# motherboard.net
KiCad netlist of a schematic drawn in EAGLE
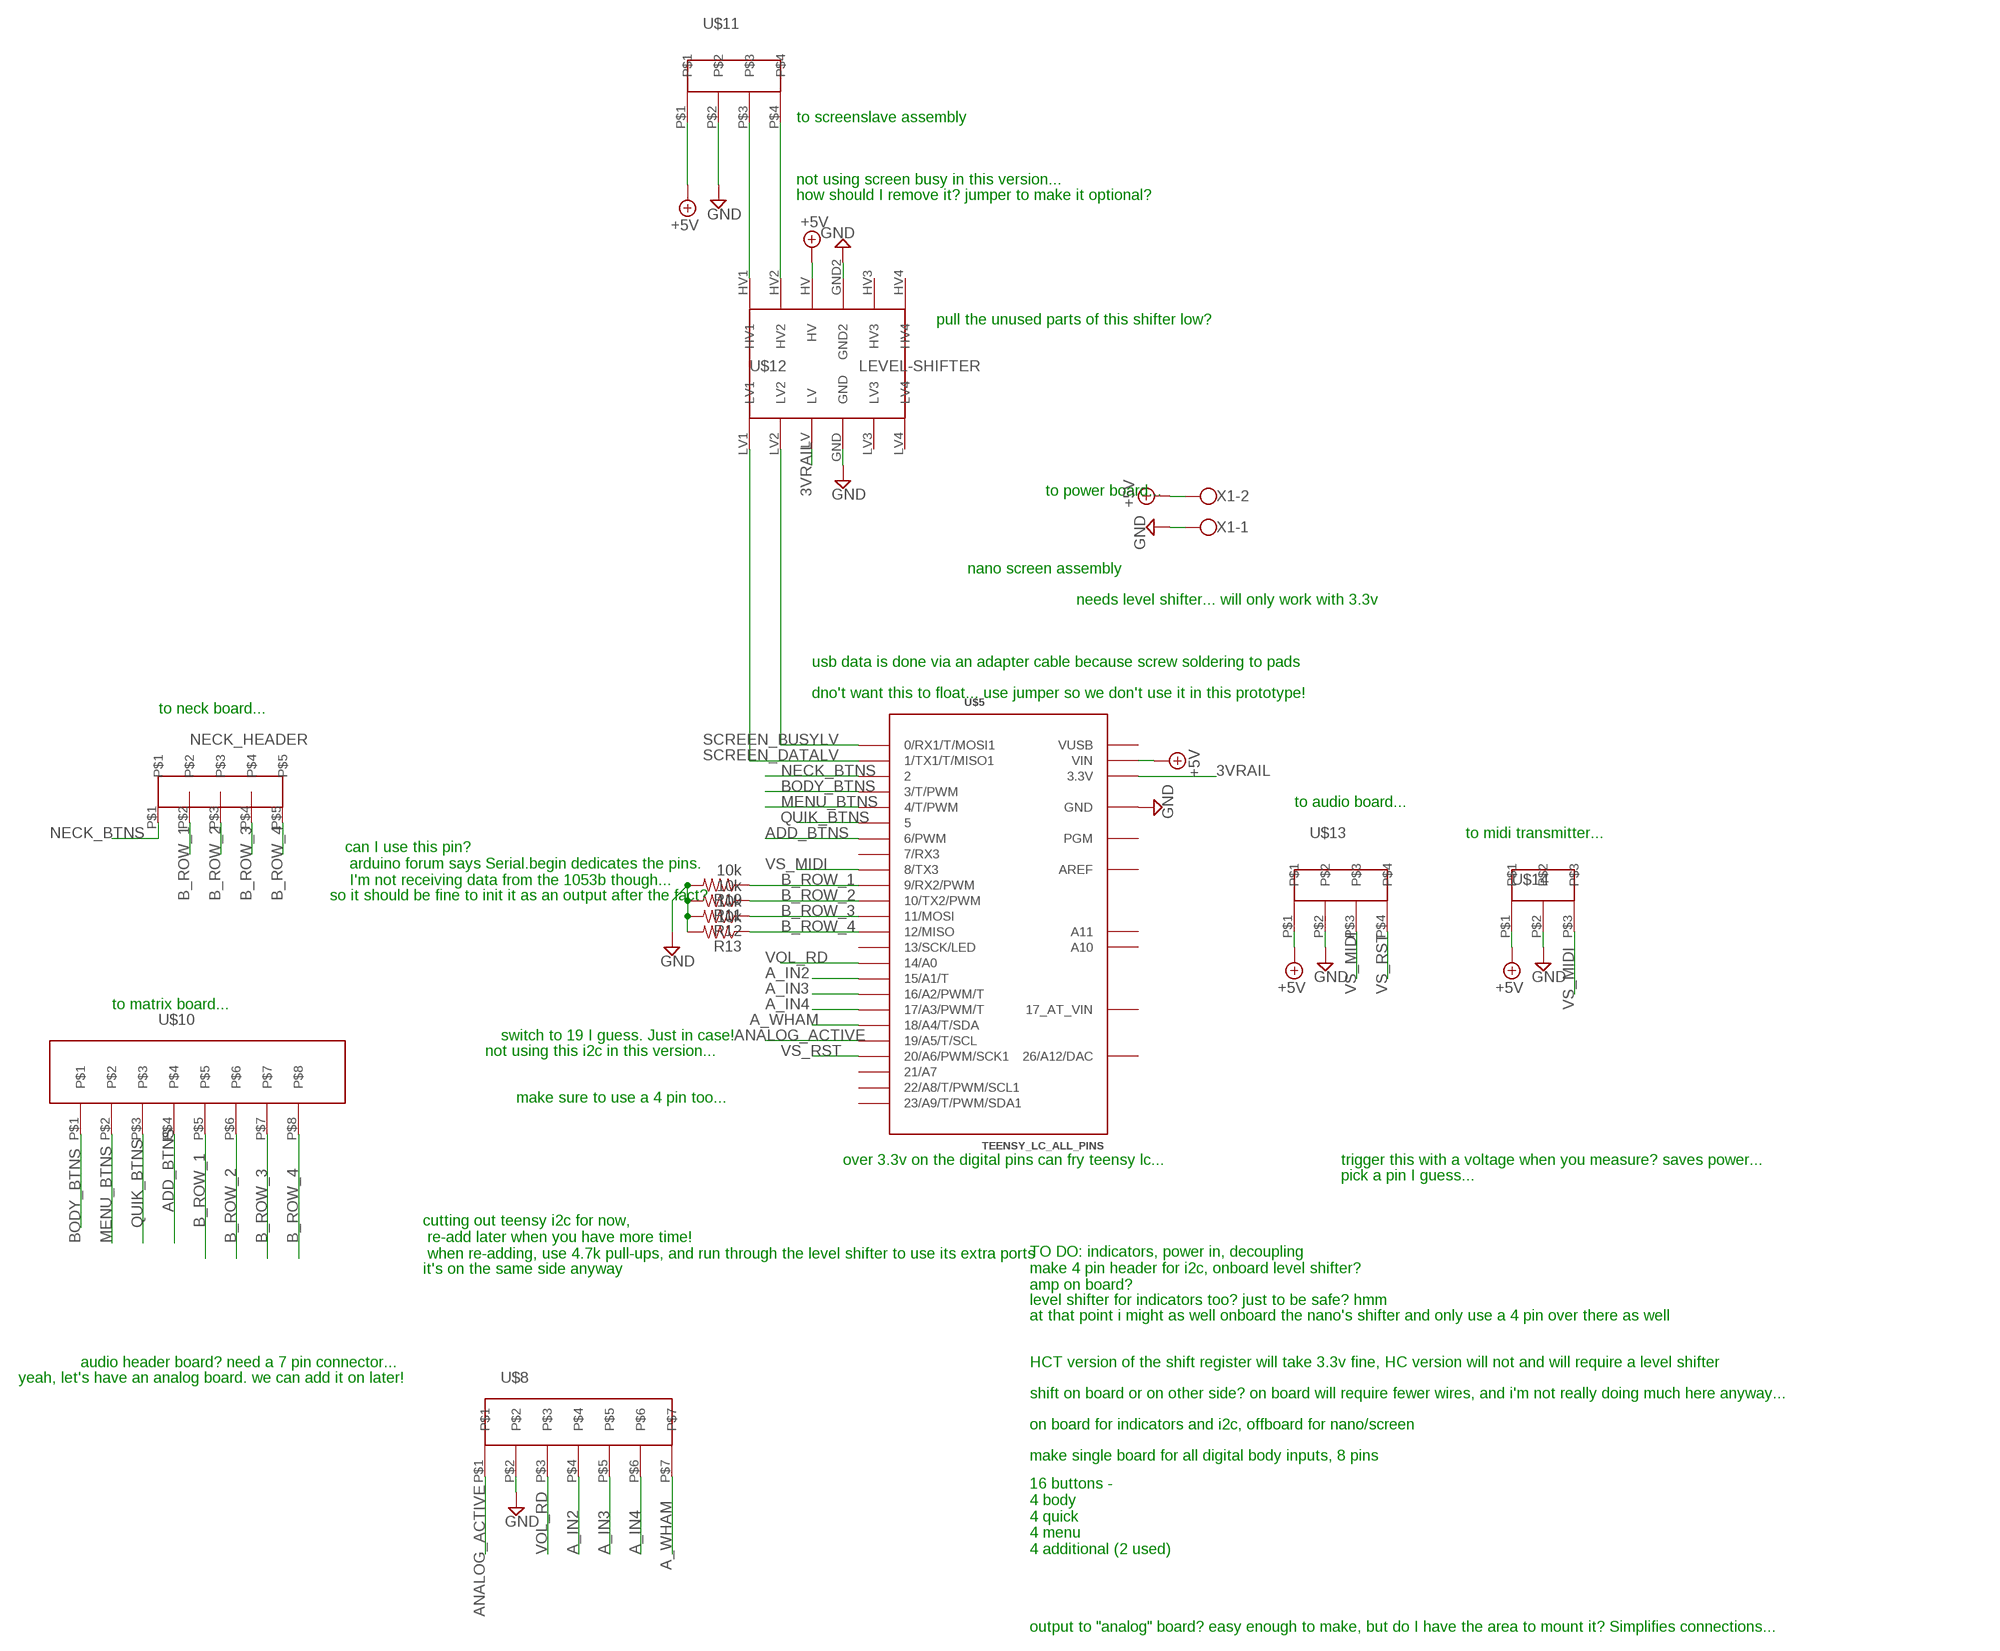
[diagram p0: schematic, sheet 1]

(export (version "E")
  (design (tool "Eeschema 10.0.6"))
  (components
    (comp (ref "NECK_HEADER")
      (value "5-PIN-HEADER")
      (footprint "eagle-import:5-PIN-HEADER")
      (libsource (lib "eagle-import") (part "5-PIN-HEADER"))
    )
    (comp (ref "R10")
      (value "10k")
      (footprint "eagle-import:0204_7")
      (libsource (lib "eagle-import") (part "R-US_0204/7"))
    )
    (comp (ref "R11")
      (value "10k")
      (footprint "eagle-import:0204_7")
      (libsource (lib "eagle-import") (part "R-US_0204/7"))
    )
    (comp (ref "R12")
      (value "10k")
      (footprint "eagle-import:0204_7")
      (libsource (lib "eagle-import") (part "R-US_0204/7"))
    )
    (comp (ref "R13")
      (value "10k")
      (footprint "eagle-import:0204_7")
      (libsource (lib "eagle-import") (part "R-US_0204/7"))
    )
    (comp (ref "U$5")
      (value "TEENSY_LC_ALL_PINS")
      (footprint "eagle-import:TEENSY_3.0-3.2&LC_ALL_PINS")
      (libsource (lib "eagle-import") (part "TEENSY_LC_ALL_PINS"))
    )
    (comp (ref "U$8")
      (value "7-PIN-HEADER")
      (footprint "eagle-import:7-PIN-HEADER")
      (libsource (lib "eagle-import") (part "7-PIN-HEADER"))
    )
    (comp (ref "U$10")
      (value "8-PIN-HEADER")
      (footprint "eagle-import:8-PIN-HEADER")
      (libsource (lib "eagle-import") (part "8-PIN-HEADER"))
    )
    (comp (ref "U$11")
      (value "4-PIN-HEADER")
      (footprint "eagle-import:4-PIN-HEADER")
      (libsource (lib "eagle-import") (part "4-PIN-HEADER"))
    )
    (comp (ref "U$12")
      (value "LEVEL-SHIFTER")
      (footprint "eagle-import:LEVEL-SHIFTER")
      (libsource (lib "eagle-import") (part "LEVEL-SHIFTER"))
    )
    (comp (ref "U$13")
      (value "4-PIN-HEADER")
      (footprint "eagle-import:4-PIN-HEADER")
      (libsource (lib "eagle-import") (part "4-PIN-HEADER"))
    )
    (comp (ref "U$14")
      (value "3-PIN-HEADER")
      (footprint "eagle-import:3-PIN-HEADER")
      (libsource (lib "eagle-import") (part "3-PIN-HEADER"))
    )
    (comp (ref "X1")
      (value "W237-102")
      (footprint "eagle-import:W237-102")
      (fields (field (name "MPN") "237-102"))
      (libsource (lib "eagle-import") (part "W237-102"))
    )
  )
  (nets
    (net (code "1") (name "+5V") (class "Default")
      (node (ref "U$11") (pin "P$1") (pinfunction "P$1_P$1") (pintype "bidirectional"))
      (node (ref "U$12") (pin "HV") (pinfunction "HV_HV") (pintype "bidirectional"))
      (node (ref "U$13") (pin "P$1") (pinfunction "P$1_P$1") (pintype "bidirectional"))
      (node (ref "U$14") (pin "P$1") (pinfunction "P$1_P$1") (pintype "bidirectional"))
      (node (ref "U$5") (pin "VIN") (pinfunction "VIN_VIN") (pintype "power_in"))
      (node (ref "X1") (pin "2") (pinfunction "KL_2") (pintype "passive"))
    )
    (net (code "2") (name "/3VRAIL") (class "Default")
      (node (ref "U$12") (pin "LV") (pinfunction "LV_LV") (pintype "bidirectional"))
      (node (ref "U$5") (pin "3.3V") (pinfunction "3.3V_3.3V") (pintype "power_in"))
      (node (ref "U$5") (pin "3.3V1") (pinfunction "3.3V_3.3V1") (pintype "power_in"))
    )
    (net (code "3") (name "/26{slash}A12{slash}DAC") (class "Default")
      (node (ref "U$5") (pin "RESET/DAC") (pinfunction "26/A12/DAC_RESET/DAC") (pintype "power_in"))
    )
    (net (code "4") (name "/ADD_BTNS") (class "Default")
      (node (ref "U$10") (pin "P$4") (pinfunction "P$4_P$4") (pintype "bidirectional"))
      (node (ref "U$5") (pin "6") (pinfunction "6/PWM_6") (pintype "bidirectional"))
    )
    (net (code "5") (name "/ANALOG_ACTIVE") (class "Default")
      (node (ref "U$5") (pin "19/A5") (pinfunction "19/A5/T/SCL_19/A5") (pintype "bidirectional"))
      (node (ref "U$8") (pin "P$1") (pinfunction "P$1_P$1") (pintype "bidirectional"))
    )
    (net (code "6") (name "/AREF") (class "Default")
      (node (ref "U$5") (pin "AREF") (pinfunction "AREF_AREF") (pintype "power_in"))
    )
    (net (code "7") (name "/A_IN2") (class "Default")
      (node (ref "U$5") (pin "15/A1") (pinfunction "15/A1/T_15/A1") (pintype "bidirectional"))
      (node (ref "U$8") (pin "P$4") (pinfunction "P$4_P$4") (pintype "bidirectional"))
    )
    (net (code "8") (name "/A_IN3") (class "Default")
      (node (ref "U$5") (pin "16/A2") (pinfunction "16/A2/PWM/T_16/A2") (pintype "bidirectional"))
      (node (ref "U$8") (pin "P$5") (pinfunction "P$5_P$5") (pintype "bidirectional"))
    )
    (net (code "9") (name "/A_IN4") (class "Default")
      (node (ref "U$5") (pin "17/A3") (pinfunction "17/A3/PWM/T_17/A3") (pintype "bidirectional"))
      (node (ref "U$8") (pin "P$6") (pinfunction "P$6_P$6") (pintype "bidirectional"))
    )
    (net (code "10") (name "/A_WHAM") (class "Default")
      (node (ref "U$5") (pin "18/A4") (pinfunction "18/A4/T/SDA_18/A4") (pintype "bidirectional"))
      (node (ref "U$8") (pin "P$7") (pinfunction "P$7_P$7") (pintype "bidirectional"))
    )
    (net (code "11") (name "/BODY_BTNS") (class "Default")
      (node (ref "U$10") (pin "P$1") (pinfunction "P$1_P$1") (pintype "bidirectional"))
      (node (ref "U$5") (pin "3") (pinfunction "3/T/PWM_3") (pintype "bidirectional"))
    )
    (net (code "12") (name "/B_ROW_1") (class "Default")
      (node (ref "NECK_HEADER") (pin "P$2") (pinfunction "P$2_P$2") (pintype "bidirectional"))
      (node (ref "R10") (pin "1") (pinfunction "1_1") (pintype "passive"))
      (node (ref "U$10") (pin "P$5") (pinfunction "P$5_P$5") (pintype "bidirectional"))
      (node (ref "U$5") (pin "9") (pinfunction "9/RX2/PWM_9") (pintype "bidirectional"))
    )
    (net (code "13") (name "/B_ROW_2") (class "Default")
      (node (ref "NECK_HEADER") (pin "P$3") (pinfunction "P$3_P$3") (pintype "bidirectional"))
      (node (ref "R11") (pin "1") (pinfunction "1_1") (pintype "passive"))
      (node (ref "U$10") (pin "P$6") (pinfunction "P$6_P$6") (pintype "bidirectional"))
      (node (ref "U$5") (pin "10") (pinfunction "10/TX2/PWM_10") (pintype "bidirectional"))
    )
    (net (code "14") (name "/B_ROW_3") (class "Default")
      (node (ref "NECK_HEADER") (pin "P$4") (pinfunction "P$4_P$4") (pintype "bidirectional"))
      (node (ref "R12") (pin "1") (pinfunction "1_1") (pintype "passive"))
      (node (ref "U$10") (pin "P$7") (pinfunction "P$7_P$7") (pintype "bidirectional"))
      (node (ref "U$5") (pin "11") (pinfunction "11/MOSI_11") (pintype "bidirectional"))
    )
    (net (code "15") (name "/B_ROW_4") (class "Default")
      (node (ref "NECK_HEADER") (pin "P$5") (pinfunction "P$5_P$5") (pintype "bidirectional"))
      (node (ref "R13") (pin "1") (pinfunction "1_1") (pintype "passive"))
      (node (ref "U$10") (pin "P$8") (pinfunction "P$8_P$8") (pintype "bidirectional"))
      (node (ref "U$5") (pin "12") (pinfunction "12/MISO_12") (pintype "bidirectional"))
    )
    (net (code "16") (name "/MENU_BTNS") (class "Default")
      (node (ref "U$10") (pin "P$2") (pinfunction "P$2_P$2") (pintype "bidirectional"))
      (node (ref "U$5") (pin "4") (pinfunction "4/T/PWM_4") (pintype "bidirectional"))
    )
    (net (code "17") (name "/NECK_BTNS") (class "Default")
      (node (ref "NECK_HEADER") (pin "P$1") (pinfunction "P$1_P$1") (pintype "bidirectional"))
      (node (ref "U$5") (pin "2") (pinfunction "2_2") (pintype "bidirectional"))
    )
    (net (code "18") (name "/QUIK_BTNS") (class "Default")
      (node (ref "U$10") (pin "P$3") (pinfunction "P$3_P$3") (pintype "bidirectional"))
      (node (ref "U$5") (pin "5") (pinfunction "5_5") (pintype "bidirectional"))
    )
    (net (code "19") (name "/SCREEN_BUSYLV") (class "Default")
      (node (ref "U$12") (pin "LV2") (pinfunction "LV2_LV2") (pintype "bidirectional"))
      (node (ref "U$5") (pin "0") (pinfunction "0/RX1/T/MOSI1_0") (pintype "bidirectional"))
    )
    (net (code "20") (name "/SCREEN_DATALV") (class "Default")
      (node (ref "U$12") (pin "LV1") (pinfunction "LV1_LV1") (pintype "bidirectional"))
      (node (ref "U$5") (pin "1") (pinfunction "1/TX1/T/MISO1_1") (pintype "bidirectional"))
    )
    (net (code "21") (name "/VOL_RD") (class "Default")
      (node (ref "U$5") (pin "14/A0") (pinfunction "14/A0_14/A0") (pintype "bidirectional"))
      (node (ref "U$8") (pin "P$3") (pinfunction "P$3_P$3") (pintype "bidirectional"))
    )
    (net (code "22") (name "/VS_MIDI") (class "Default")
      (node (ref "U$13") (pin "P$3") (pinfunction "P$3_P$3") (pintype "bidirectional"))
      (node (ref "U$14") (pin "P$3") (pinfunction "P$3_P$3") (pintype "bidirectional"))
      (node (ref "U$5") (pin "8") (pinfunction "8/TX3_8") (pintype "bidirectional"))
    )
    (net (code "23") (name "/VS_RST") (class "Default")
      (node (ref "U$13") (pin "P$4") (pinfunction "P$4_P$4") (pintype "bidirectional"))
      (node (ref "U$5") (pin "20/A6") (pinfunction "20/A6/PWM/SCK1_20/A6") (pintype "bidirectional"))
    )
    (net (code "24") (name "/VUSB") (class "Default")
      (node (ref "U$5") (pin "VUSB") (pinfunction "VUSB_VUSB") (pintype "power_in"))
    )
    (net (code "25") (name "GND") (class "Default")
      (node (ref "R10") (pin "2") (pinfunction "2_2") (pintype "passive"))
      (node (ref "R11") (pin "2") (pinfunction "2_2") (pintype "passive"))
      (node (ref "R12") (pin "2") (pinfunction "2_2") (pintype "passive"))
      (node (ref "R13") (pin "2") (pinfunction "2_2") (pintype "passive"))
      (node (ref "U$11") (pin "P$2") (pinfunction "P$2_P$2") (pintype "bidirectional"))
      (node (ref "U$12") (pin "GND") (pinfunction "GND_GND") (pintype "bidirectional"))
      (node (ref "U$12") (pin "GND2") (pinfunction "GND2_GND2") (pintype "bidirectional"))
      (node (ref "U$13") (pin "P$2") (pinfunction "P$2_P$2") (pintype "bidirectional"))
      (node (ref "U$14") (pin "P$2") (pinfunction "P$2_P$2") (pintype "bidirectional"))
      (node (ref "U$5") (pin "AGND") (pinfunction "GND_AGND") (pintype "power_in"))
      (node (ref "U$5") (pin "GND") (pinfunction "GND_GND") (pintype "power_in"))
      (node (ref "U$5") (pin "GND1") (pinfunction "GND_GND1") (pintype "power_in"))
      (node (ref "U$8") (pin "P$2") (pinfunction "P$2_P$2") (pintype "bidirectional"))
      (node (ref "X1") (pin "1") (pinfunction "KL_1") (pintype "passive"))
    )
    (net (code "26") (name "Net-(U$11-PadP$3)") (class "Default")
      (node (ref "U$11") (pin "P$3") (pinfunction "P$3_P$3") (pintype "bidirectional"))
      (node (ref "U$12") (pin "HV1") (pinfunction "HV1_HV1") (pintype "bidirectional"))
    )
    (net (code "27") (name "Net-(U$11-PadP$4)") (class "Default")
      (node (ref "U$11") (pin "P$4") (pinfunction "P$4_P$4") (pintype "bidirectional"))
      (node (ref "U$12") (pin "HV2") (pinfunction "HV2_HV2") (pintype "bidirectional"))
    )
    (net (code "28") (name "unconnected-(U$5-7{slash}RX3-Pad7)") (class "Default")
      (node (ref "U$5") (pin "7") (pinfunction "7/RX3_7") (pintype "bidirectional"))
    )
    (net (code "29") (name "unconnected-(U$5-13{slash}SCK{slash}LED-Pad13)") (class "Default")
      (node (ref "U$5") (pin "13") (pinfunction "13/SCK/LED_13") (pintype "bidirectional"))
    )
    (net (code "30") (name "unconnected-(U$5-17_AT_VIN-PadVBAT)") (class "Default")
      (node (ref "U$5") (pin "VBAT") (pinfunction "17_AT_VIN_VBAT") (pintype "bidirectional"))
    )
    (net (code "31") (name "unconnected-(U$5-22{slash}A8{slash}T{slash}PWM{slash}SCL1-Pad22{slash}A8)") (class "Default")
      (node (ref "U$5") (pin "22/A8") (pinfunction "22/A8/T/PWM/SCL1_22/A8") (pintype "bidirectional"))
    )
    (net (code "32") (name "unconnected-(U$5-23{slash}A9{slash}T{slash}PWM{slash}SDA1-Pad23{slash}A9)") (class "Default")
      (node (ref "U$5") (pin "23/A9") (pinfunction "23/A9/T/PWM/SDA1_23/A9") (pintype "bidirectional"))
    )
    (net (code "33") (name "unconnected-(U$5-Pad21{slash}A7)") (class "Default")
      (node (ref "U$5") (pin "21/A7") (pinfunction "21/A7_21/A7") (pintype "bidirectional"))
    )
    (net (code "34") (name "unconnected-(U$5-PadA10)") (class "Default")
      (node (ref "U$5") (pin "A10") (pinfunction "A10_A10") (pintype "bidirectional"))
    )
    (net (code "35") (name "unconnected-(U$5-PadA11)") (class "Default")
      (node (ref "U$5") (pin "A11") (pinfunction "A11_A11") (pintype "bidirectional"))
    )
    (net (code "36") (name "unconnected-(U$5-PadPGM)") (class "Default")
      (node (ref "U$5") (pin "PGM") (pinfunction "PGM_PGM") (pintype "bidirectional"))
    )
    (net (code "37") (name "unconnected-(U$12-PadHV3)") (class "Default")
      (node (ref "U$12") (pin "HV3") (pinfunction "HV3_HV3") (pintype "bidirectional"))
    )
    (net (code "38") (name "unconnected-(U$12-PadHV4)") (class "Default")
      (node (ref "U$12") (pin "HV4") (pinfunction "HV4_HV4") (pintype "bidirectional"))
    )
    (net (code "39") (name "unconnected-(U$12-PadLV3)") (class "Default")
      (node (ref "U$12") (pin "LV3") (pinfunction "LV3_LV3") (pintype "bidirectional"))
    )
    (net (code "40") (name "unconnected-(U$12-PadLV4)") (class "Default")
      (node (ref "U$12") (pin "LV4") (pinfunction "LV4_LV4") (pintype "bidirectional"))
    )
  )
)
